# Access_ID.net
KiCad netlist of a schematic drawn in EAGLE
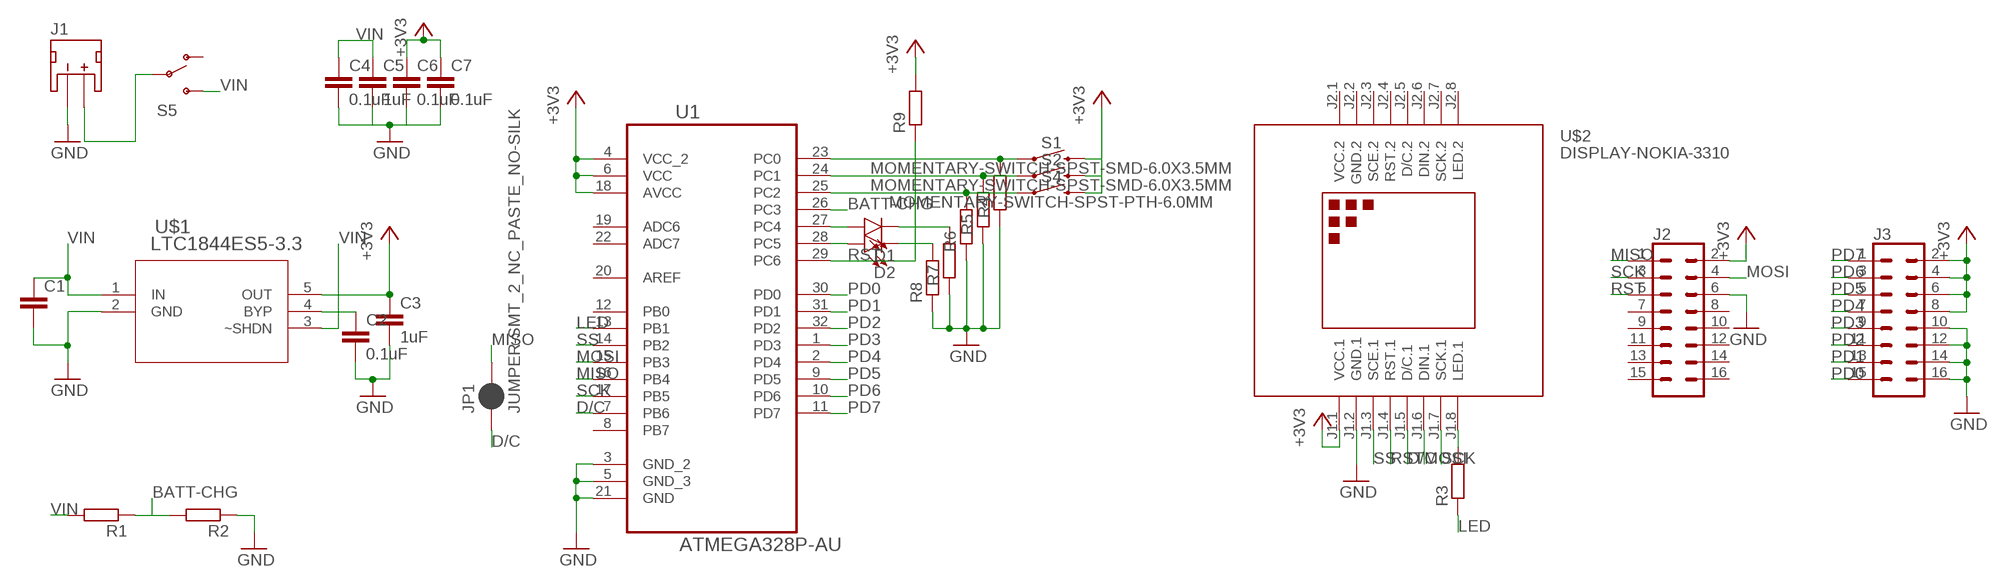
[diagram p0: schematic, sheet 1]

(export (version "E")
  (design (tool "Eeschema 10.0.6"))
  (components
    (comp (ref "C1")
      (value "C-EUC0603K")
      (footprint "eagle-import:C0603K")
      (libsource (lib "eagle-import") (part "C-EUC0603K"))
    )
    (comp (ref "C2")
      (value "0.1uF")
      (footprint "eagle-import:C0603K")
      (libsource (lib "eagle-import") (part "C-EUC0603K"))
    )
    (comp (ref "C3")
      (value "1uF")
      (footprint "eagle-import:C0603K")
      (libsource (lib "eagle-import") (part "C-EUC0603K"))
    )
    (comp (ref "C4")
      (value "0.1uF")
      (footprint "eagle-import:C0603K")
      (libsource (lib "eagle-import") (part "C-EUC0603K"))
    )
    (comp (ref "C5")
      (value "1uF")
      (footprint "eagle-import:C0603K")
      (libsource (lib "eagle-import") (part "C-EUC0603K"))
    )
    (comp (ref "C6")
      (value "0.1uF")
      (footprint "eagle-import:C0603K")
      (libsource (lib "eagle-import") (part "C-EUC0603K"))
    )
    (comp (ref "C7")
      (value "0.1uF")
      (footprint "eagle-import:C0603K")
      (libsource (lib "eagle-import") (part "C-EUC0603K"))
    )
    (comp (ref "D1")
      (value "LED0603")
      (footprint "eagle-import:LED-0603")
      (libsource (lib "eagle-import") (part "LED0603"))
    )
    (comp (ref "D2")
      (value "LED0603")
      (footprint "eagle-import:LED-0603")
      (libsource (lib "eagle-import") (part "LED0603"))
    )
    (comp (ref "J1")
      (value "JST_2MM_MALE")
      (footprint "eagle-import:JST-2-SMD")
      (libsource (lib "eagle-import") (part "JST_2MM_MALE"))
    )
    (comp (ref "J2")
      (value "CONN_08X2")
      (footprint "eagle-import:2X8")
      (libsource (lib "eagle-import") (part "CONN_08X2"))
    )
    (comp (ref "J3")
      (value "CONN_08X2")
      (footprint "eagle-import:2X8")
      (libsource (lib "eagle-import") (part "CONN_08X2"))
    )
    (comp (ref "JP1")
      (value "JUMPER-SMT_2_NC_PASTE_NO-SILK")
      (footprint "eagle-import:SMT-JUMPER_2_NC_PASTE_NO-SILK")
      (libsource (lib "eagle-import") (part "JUMPER-SMT_2_NC_PASTE_NO-SILK"))
    )
    (comp (ref "R1")
      (value "R-EU_R0603")
      (footprint "eagle-import:R0603")
      (libsource (lib "eagle-import") (part "resistor_348_R-EU_R0603"))
    )
    (comp (ref "R2")
      (value "R-EU_R0603")
      (footprint "eagle-import:R0603")
      (libsource (lib "eagle-import") (part "resistor_348_R-EU_R0603"))
    )
    (comp (ref "R3")
      (value "R-EU_R0603")
      (footprint "eagle-import:R0603")
      (libsource (lib "eagle-import") (part "resistor_348_R-EU_R0603"))
    )
    (comp (ref "R4")
      (value "R-EU_R0603")
      (footprint "eagle-import:R0603")
      (libsource (lib "eagle-import") (part "R-EU_R0603"))
    )
    (comp (ref "R5")
      (value "R-EU_R0603")
      (footprint "eagle-import:R0603")
      (libsource (lib "eagle-import") (part "R-EU_R0603"))
    )
    (comp (ref "R6")
      (value "R-EU_R0603")
      (footprint "eagle-import:R0603")
      (libsource (lib "eagle-import") (part "R-EU_R0603"))
    )
    (comp (ref "R7")
      (value "R-EU_R0603")
      (footprint "eagle-import:R0603")
      (libsource (lib "eagle-import") (part "R-EU_R0603"))
    )
    (comp (ref "R8")
      (value "R-EU_R0603")
      (footprint "eagle-import:R0603")
      (libsource (lib "eagle-import") (part "R-EU_R0603"))
    )
    (comp (ref "R9")
      (value "R-EU_R0603")
      (footprint "eagle-import:R0603")
      (libsource (lib "eagle-import") (part "R-EU_R0603"))
    )
    (comp (ref "S1")
      (value "MOMENTARY-SWITCH-SPST-SMD-6.0X3.5MM")
      (footprint "eagle-import:TACTILE_SWITCH_SMD_6.0X3.5MM")
      (libsource (lib "eagle-import") (part "MOMENTARY-SWITCH-SPST-SMD-6.0X3.5MM"))
    )
    (comp (ref "S2")
      (value "MOMENTARY-SWITCH-SPST-SMD-6.0X3.5MM")
      (footprint "eagle-import:TACTILE_SWITCH_SMD_6.0X3.5MM")
      (libsource (lib "eagle-import") (part "MOMENTARY-SWITCH-SPST-SMD-6.0X3.5MM"))
    )
    (comp (ref "S4")
      (value "MOMENTARY-SWITCH-SPST-PTH-6.0MM")
      (footprint "eagle-import:TACTILE_SWITCH_PTH_6.0MM")
      (libsource (lib "eagle-import") (part "MOMENTARY-SWITCH-SPST-PTH-6.0MM"))
    )
    (comp (ref "S5")
      (value "SWITCH-SPDT-SMD-A")
      (footprint "eagle-import:SWITCH-SPST-SMD-A")
      (libsource (lib "eagle-import") (part "SWITCH-SPDT-SMD-A"))
    )
    (comp (ref "U$1")
      (value "LTC1844ES5-3.3")
      (footprint "eagle-import:TSOT-23_S5")
      (libsource (lib "eagle-import") (part "LTC1844ES5-3.3"))
    )
    (comp (ref "U$2")
      (value "DISPLAY-NOKIA-3310")
      (footprint "eagle-import:DISPLAY-NOKIA-3310")
      (libsource (lib "eagle-import") (part "DISPLAY-NOKIA-3310"))
    )
    (comp (ref "U1")
      (value "ATMEGA328P-AU")
      (footprint "eagle-import:QFP80P900X900X120-32N")
      (libsource (lib "eagle-import") (part "ATMEGA328P-AU"))
    )
  )
  (nets
    (net (code "1") (name "+3V3") (class "Default")
      (node (ref "C3") (pin "1") (pinfunction "1_1") (pintype "passive"))
      (node (ref "C6") (pin "1") (pinfunction "1_1") (pintype "passive"))
      (node (ref "C7") (pin "1") (pinfunction "1_1") (pintype "passive"))
      (node (ref "J2") (pin "2") (pinfunction "2_2") (pintype "passive"))
      (node (ref "J3") (pin "2") (pinfunction "2_2") (pintype "passive"))
      (node (ref "J3") (pin "4") (pinfunction "4_4") (pintype "passive"))
      (node (ref "J3") (pin "6") (pinfunction "6_6") (pintype "passive"))
      (node (ref "J3") (pin "8") (pinfunction "8_8") (pintype "passive"))
      (node (ref "R9") (pin "2") (pinfunction "2_2") (pintype "passive"))
      (node (ref "S1") (pin "2") (pinfunction "2_2") (pintype "passive"))
      (node (ref "S2") (pin "2") (pinfunction "2_2") (pintype "passive"))
      (node (ref "S4") (pin "3") (pinfunction "2_3") (pintype "passive"))
      (node (ref "U$1") (pin "5") (pinfunction "OUT_5") (pintype "passive"))
      (node (ref "U$2") (pin "J1.1") (pinfunction "VCC.1_J1.1") (pintype "power_in"))
      (node (ref "U1") (pin "18") (pinfunction "AVCC_18") (pintype "power_in"))
      (node (ref "U1") (pin "4") (pinfunction "VCC_2_4") (pintype "power_in"))
      (node (ref "U1") (pin "6") (pinfunction "VCC_6") (pintype "power_in"))
    )
    (net (code "2") (name "/BATT-CHG") (class "Default")
      (node (ref "R1") (pin "1") (pinfunction "1_1") (pintype "passive"))
      (node (ref "R2") (pin "2") (pinfunction "2_2") (pintype "passive"))
      (node (ref "U1") (pin "26") (pinfunction "PC3_26") (pintype "bidirectional"))
    )
    (net (code "3") (name "/D{slash}C") (class "Default")
      (node (ref "JP1") (pin "1") (pinfunction "1_1") (pintype "passive"))
      (node (ref "U$2") (pin "J1.5") (pinfunction "D/C.1_J1.5") (pintype "bidirectional"))
      (node (ref "U1") (pin "7") (pinfunction "PB6_7") (pintype "bidirectional"))
    )
    (net (code "4") (name "/GND.2") (class "Default")
      (node (ref "U$2") (pin "J2.2") (pinfunction "GND.2_J2.2") (pintype "power_in"))
    )
    (net (code "5") (name "/LED") (class "Default")
      (node (ref "R3") (pin "1") (pinfunction "1_1") (pintype "passive"))
      (node (ref "U1") (pin "13") (pinfunction "PB1_13") (pintype "bidirectional"))
    )
    (net (code "6") (name "/MISO") (class "Default")
      (node (ref "J2") (pin "1") (pinfunction "1_1") (pintype "passive"))
      (node (ref "JP1") (pin "2") (pinfunction "2_2") (pintype "passive"))
      (node (ref "U1") (pin "16") (pinfunction "PB4_16") (pintype "bidirectional"))
    )
    (net (code "7") (name "/MOSI") (class "Default")
      (node (ref "J2") (pin "4") (pinfunction "4_4") (pintype "passive"))
      (node (ref "U$2") (pin "J1.6") (pinfunction "DIN.1_J1.6") (pintype "bidirectional"))
      (node (ref "U1") (pin "15") (pinfunction "PB3_15") (pintype "bidirectional"))
    )
    (net (code "8") (name "/PD0") (class "Default")
      (node (ref "J3") (pin "15") (pinfunction "15_15") (pintype "passive"))
      (node (ref "U1") (pin "30") (pinfunction "PD0_30") (pintype "bidirectional"))
    )
    (net (code "9") (name "/PD1") (class "Default")
      (node (ref "J3") (pin "13") (pinfunction "13_13") (pintype "passive"))
      (node (ref "U1") (pin "31") (pinfunction "PD1_31") (pintype "bidirectional"))
    )
    (net (code "10") (name "/PD2") (class "Default")
      (node (ref "J3") (pin "11") (pinfunction "11_11") (pintype "passive"))
      (node (ref "U1") (pin "32") (pinfunction "PD2_32") (pintype "bidirectional"))
    )
    (net (code "11") (name "/PD3") (class "Default")
      (node (ref "J3") (pin "9") (pinfunction "9_9") (pintype "passive"))
      (node (ref "U1") (pin "1") (pinfunction "PD3_1") (pintype "bidirectional"))
    )
    (net (code "12") (name "/PD4") (class "Default")
      (node (ref "J3") (pin "7") (pinfunction "7_7") (pintype "passive"))
      (node (ref "U1") (pin "2") (pinfunction "PD4_2") (pintype "bidirectional"))
    )
    (net (code "13") (name "/PD5") (class "Default")
      (node (ref "J3") (pin "5") (pinfunction "5_5") (pintype "passive"))
      (node (ref "U1") (pin "9") (pinfunction "PD5_9") (pintype "bidirectional"))
    )
    (net (code "14") (name "/PD6") (class "Default")
      (node (ref "J3") (pin "3") (pinfunction "3_3") (pintype "passive"))
      (node (ref "U1") (pin "10") (pinfunction "PD6_10") (pintype "bidirectional"))
    )
    (net (code "15") (name "/PD7") (class "Default")
      (node (ref "J3") (pin "1") (pinfunction "1_1") (pintype "passive"))
      (node (ref "U1") (pin "11") (pinfunction "PD7_11") (pintype "bidirectional"))
    )
    (net (code "16") (name "/RST") (class "Default")
      (node (ref "J2") (pin "5") (pinfunction "5_5") (pintype "passive"))
      (node (ref "R9") (pin "1") (pinfunction "1_1") (pintype "passive"))
      (node (ref "U$2") (pin "J1.4") (pinfunction "RST.1_J1.4") (pintype "bidirectional"))
      (node (ref "U1") (pin "29") (pinfunction "PC6_29") (pintype "bidirectional"))
    )
    (net (code "17") (name "/SCK") (class "Default")
      (node (ref "J2") (pin "3") (pinfunction "3_3") (pintype "passive"))
      (node (ref "U$2") (pin "J1.7") (pinfunction "SCK.1_J1.7") (pintype "bidirectional"))
      (node (ref "U1") (pin "17") (pinfunction "PB5_17") (pintype "bidirectional"))
    )
    (net (code "18") (name "/SS") (class "Default")
      (node (ref "U$2") (pin "J1.3") (pinfunction "SCE.1_J1.3") (pintype "bidirectional"))
      (node (ref "U1") (pin "14") (pinfunction "PB2_14") (pintype "bidirectional"))
    )
    (net (code "19") (name "/VCC.2") (class "Default")
      (node (ref "U$2") (pin "J2.1") (pinfunction "VCC.2_J2.1") (pintype "power_in"))
    )
    (net (code "20") (name "/VIN") (class "Default")
      (node (ref "C1") (pin "1") (pinfunction "1_1") (pintype "passive"))
      (node (ref "C4") (pin "1") (pinfunction "1_1") (pintype "passive"))
      (node (ref "C5") (pin "1") (pinfunction "1_1") (pintype "passive"))
      (node (ref "R1") (pin "2") (pinfunction "2_2") (pintype "passive"))
      (node (ref "S5") (pin "3") (pinfunction "S_3") (pintype "passive"))
      (node (ref "U$1") (pin "1") (pinfunction "IN_1") (pintype "passive"))
      (node (ref "U$1") (pin "3") (pinfunction "~{SHDN}_3") (pintype "passive"))
    )
    (net (code "21") (name "GND") (class "Default")
      (node (ref "C1") (pin "2") (pinfunction "2_2") (pintype "passive"))
      (node (ref "C2") (pin "2") (pinfunction "2_2") (pintype "passive"))
      (node (ref "C3") (pin "2") (pinfunction "2_2") (pintype "passive"))
      (node (ref "C4") (pin "2") (pinfunction "2_2") (pintype "passive"))
      (node (ref "C5") (pin "2") (pinfunction "2_2") (pintype "passive"))
      (node (ref "C6") (pin "2") (pinfunction "2_2") (pintype "passive"))
      (node (ref "C7") (pin "2") (pinfunction "2_2") (pintype "passive"))
      (node (ref "J1") (pin "1") (pinfunction "-_1") (pintype "bidirectional"))
      (node (ref "J2") (pin "6") (pinfunction "6_6") (pintype "passive"))
      (node (ref "J3") (pin "10") (pinfunction "10_10") (pintype "passive"))
      (node (ref "J3") (pin "12") (pinfunction "12_12") (pintype "passive"))
      (node (ref "J3") (pin "14") (pinfunction "14_14") (pintype "passive"))
      (node (ref "J3") (pin "16") (pinfunction "16_16") (pintype "passive"))
      (node (ref "R2") (pin "1") (pinfunction "1_1") (pintype "passive"))
      (node (ref "R4") (pin "1") (pinfunction "1_1") (pintype "passive"))
      (node (ref "R5") (pin "1") (pinfunction "1_1") (pintype "passive"))
      (node (ref "R6") (pin "1") (pinfunction "1_1") (pintype "passive"))
      (node (ref "R7") (pin "1") (pinfunction "1_1") (pintype "passive"))
      (node (ref "R8") (pin "1") (pinfunction "1_1") (pintype "passive"))
      (node (ref "U$1") (pin "2") (pinfunction "GND_2") (pintype "passive"))
      (node (ref "U$2") (pin "J1.2") (pinfunction "GND.1_J1.2") (pintype "power_in"))
      (node (ref "U1") (pin "21") (pinfunction "GND_21") (pintype "passive"))
      (node (ref "U1") (pin "3") (pinfunction "GND_2_3") (pintype "passive"))
      (node (ref "U1") (pin "5") (pinfunction "GND_3_5") (pintype "passive"))
    )
    (net (code "22") (name "Net-(D1-PadC)") (class "Default")
      (node (ref "D1") (pin "C") (pinfunction "C_C") (pintype "passive"))
      (node (ref "R7") (pin "2") (pinfunction "2_2") (pintype "passive"))
    )
    (net (code "23") (name "Net-(D2-PadC)") (class "Default")
      (node (ref "D2") (pin "C") (pinfunction "C_C") (pintype "passive"))
      (node (ref "R8") (pin "2") (pinfunction "2_2") (pintype "passive"))
    )
    (net (code "24") (name "Net-(J1-+)") (class "Default")
      (node (ref "J1") (pin "2") (pinfunction "+_2") (pintype "bidirectional"))
      (node (ref "S5") (pin "2") (pinfunction "P_2") (pintype "passive"))
    )
    (net (code "25") (name "Net-(U$1-BYP)") (class "Default")
      (node (ref "C2") (pin "1") (pinfunction "1_1") (pintype "passive"))
      (node (ref "U$1") (pin "4") (pinfunction "BYP_4") (pintype "passive"))
    )
    (net (code "26") (name "Net-(U$2-LED.1)") (class "Default")
      (node (ref "R3") (pin "2") (pinfunction "2_2") (pintype "passive"))
      (node (ref "U$2") (pin "J1.8") (pinfunction "LED.1_J1.8") (pintype "input"))
    )
    (net (code "27") (name "Net-(U1-PC0)") (class "Default")
      (node (ref "R4") (pin "2") (pinfunction "2_2") (pintype "passive"))
      (node (ref "S1") (pin "1") (pinfunction "1_1") (pintype "passive"))
      (node (ref "U1") (pin "23") (pinfunction "PC0_23") (pintype "bidirectional"))
    )
    (net (code "28") (name "Net-(U1-PC1)") (class "Default")
      (node (ref "R5") (pin "2") (pinfunction "2_2") (pintype "passive"))
      (node (ref "S2") (pin "1") (pinfunction "1_1") (pintype "passive"))
      (node (ref "U1") (pin "24") (pinfunction "PC1_24") (pintype "bidirectional"))
    )
    (net (code "29") (name "Net-(U1-PC2)") (class "Default")
      (node (ref "R6") (pin "2") (pinfunction "2_2") (pintype "passive"))
      (node (ref "S4") (pin "1") (pinfunction "1_1") (pintype "passive"))
      (node (ref "U1") (pin "25") (pinfunction "PC2_25") (pintype "bidirectional"))
    )
    (net (code "30") (name "Net-(U1-PC4)") (class "Default")
      (node (ref "D1") (pin "A") (pinfunction "A_A") (pintype "passive"))
      (node (ref "U1") (pin "27") (pinfunction "PC4_27") (pintype "bidirectional"))
    )
    (net (code "31") (name "Net-(U1-PC5)") (class "Default")
      (node (ref "D2") (pin "A") (pinfunction "A_A") (pintype "passive"))
      (node (ref "U1") (pin "28") (pinfunction "PC5_28") (pintype "bidirectional"))
    )
    (net (code "32") (name "unconnected-(J1-PAD1-PadNC1)") (class "Default")
      (node (ref "J1") (pin "NC1") (pinfunction "PAD1_NC1") (pintype "bidirectional"))
    )
    (net (code "33") (name "unconnected-(J1-PAD2-PadNC2)") (class "Default")
      (node (ref "J1") (pin "NC2") (pinfunction "PAD2_NC2") (pintype "bidirectional"))
    )
    (net (code "34") (name "unconnected-(J2-Pad7)") (class "Default")
      (node (ref "J2") (pin "7") (pinfunction "7_7") (pintype "passive"))
    )
    (net (code "35") (name "unconnected-(J2-Pad8)") (class "Default")
      (node (ref "J2") (pin "8") (pinfunction "8_8") (pintype "passive"))
    )
    (net (code "36") (name "unconnected-(J2-Pad9)") (class "Default")
      (node (ref "J2") (pin "9") (pinfunction "9_9") (pintype "passive"))
    )
    (net (code "37") (name "unconnected-(J2-Pad10)") (class "Default")
      (node (ref "J2") (pin "10") (pinfunction "10_10") (pintype "passive"))
    )
    (net (code "38") (name "unconnected-(J2-Pad11)") (class "Default")
      (node (ref "J2") (pin "11") (pinfunction "11_11") (pintype "passive"))
    )
    (net (code "39") (name "unconnected-(J2-Pad12)") (class "Default")
      (node (ref "J2") (pin "12") (pinfunction "12_12") (pintype "passive"))
    )
    (net (code "40") (name "unconnected-(J2-Pad13)") (class "Default")
      (node (ref "J2") (pin "13") (pinfunction "13_13") (pintype "passive"))
    )
    (net (code "41") (name "unconnected-(J2-Pad14)") (class "Default")
      (node (ref "J2") (pin "14") (pinfunction "14_14") (pintype "passive"))
    )
    (net (code "42") (name "unconnected-(J2-Pad15)") (class "Default")
      (node (ref "J2") (pin "15") (pinfunction "15_15") (pintype "passive"))
    )
    (net (code "43") (name "unconnected-(J2-Pad16)") (class "Default")
      (node (ref "J2") (pin "16") (pinfunction "16_16") (pintype "passive"))
    )
    (net (code "44") (name "unconnected-(S5-O-Pad1)") (class "Default")
      (node (ref "S5") (pin "1") (pinfunction "O_1") (pintype "passive"))
    )
    (net (code "45") (name "unconnected-(U$2-DIN.2-PadJ2.6)") (class "Default")
      (node (ref "U$2") (pin "J2.6") (pinfunction "DIN.2_J2.6") (pintype "bidirectional"))
    )
    (net (code "46") (name "unconnected-(U$2-D{slash}C.2-PadJ2.5)") (class "Default")
      (node (ref "U$2") (pin "J2.5") (pinfunction "D/C.2_J2.5") (pintype "bidirectional"))
    )
    (net (code "47") (name "unconnected-(U$2-LED.2-PadJ2.8)") (class "Default")
      (node (ref "U$2") (pin "J2.8") (pinfunction "LED.2_J2.8") (pintype "input"))
    )
    (net (code "48") (name "unconnected-(U$2-RST.2-PadJ2.4)") (class "Default")
      (node (ref "U$2") (pin "J2.4") (pinfunction "RST.2_J2.4") (pintype "bidirectional"))
    )
    (net (code "49") (name "unconnected-(U$2-SCE.2-PadJ2.3)") (class "Default")
      (node (ref "U$2") (pin "J2.3") (pinfunction "SCE.2_J2.3") (pintype "bidirectional"))
    )
    (net (code "50") (name "unconnected-(U$2-SCK.2-PadJ2.7)") (class "Default")
      (node (ref "U$2") (pin "J2.7") (pinfunction "SCK.2_J2.7") (pintype "bidirectional"))
    )
    (net (code "51") (name "unconnected-(U1-ADC6-Pad19)") (class "Default")
      (node (ref "U1") (pin "19") (pinfunction "ADC6_19") (pintype "input"))
    )
    (net (code "52") (name "unconnected-(U1-ADC7-Pad22)") (class "Default")
      (node (ref "U1") (pin "22") (pinfunction "ADC7_22") (pintype "input"))
    )
    (net (code "53") (name "unconnected-(U1-AREF-Pad20)") (class "Default")
      (node (ref "U1") (pin "20") (pinfunction "AREF_20") (pintype "input"))
    )
    (net (code "54") (name "unconnected-(U1-PB0-Pad12)") (class "Default")
      (node (ref "U1") (pin "12") (pinfunction "PB0_12") (pintype "bidirectional"))
    )
    (net (code "55") (name "unconnected-(U1-PB7-Pad8)") (class "Default")
      (node (ref "U1") (pin "8") (pinfunction "PB7_8") (pintype "bidirectional"))
    )
  )
)
